# uDev_C8051.net
KiCad netlist of a schematic drawn in EAGLE
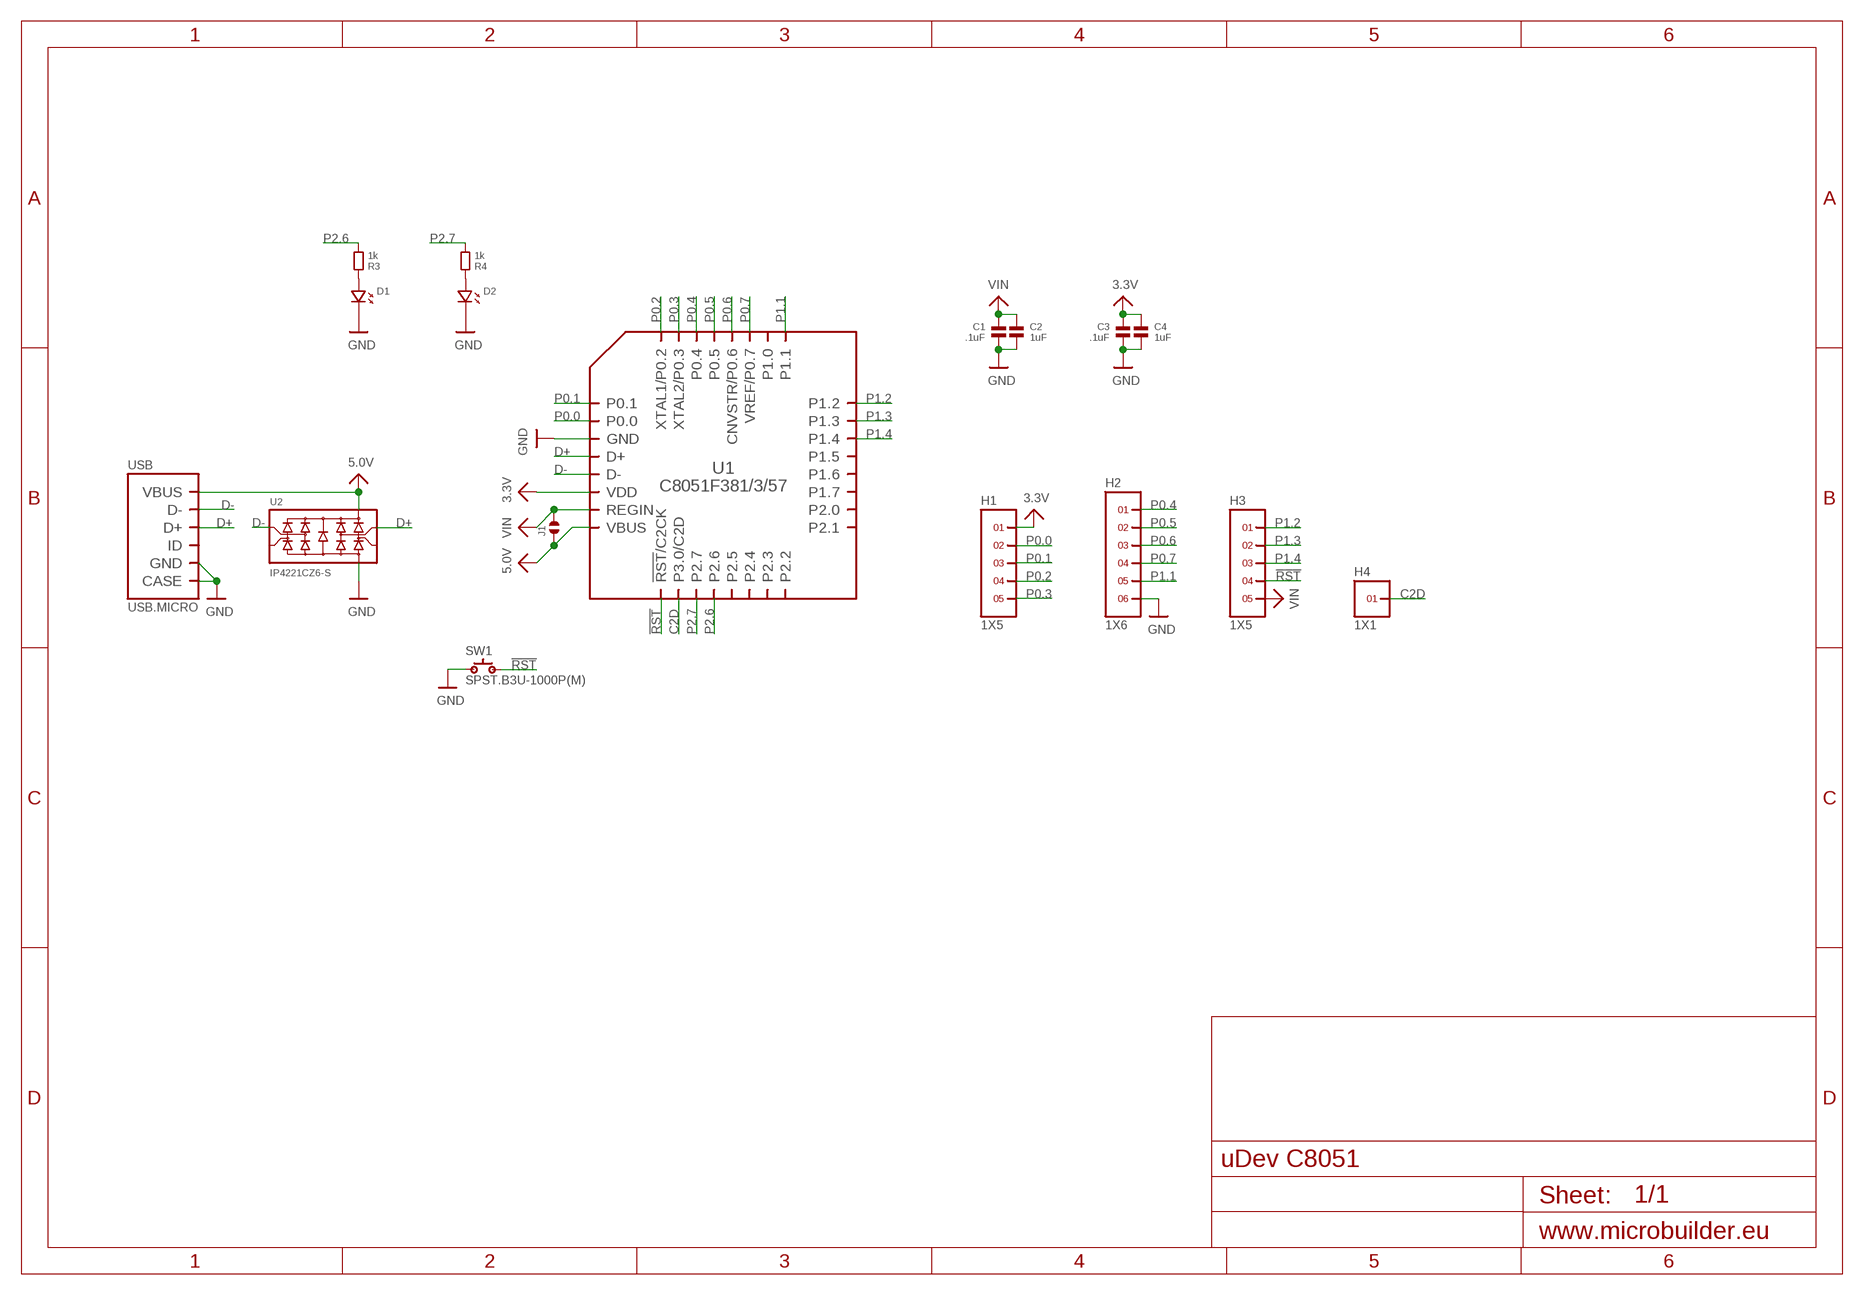
[diagram p0: schematic, sheet 1]

(export (version "E")
  (design (tool "Eeschema 10.0.6"))
  (components
    (comp (ref "C1")
      (value ".1uF")
      (footprint "eagle-import:0402")
      (libsource (lib "eagle-import") (part "CAPACITOR.0402"))
    )
    (comp (ref "C2")
      (value "1uF")
      (footprint "eagle-import:0402")
      (libsource (lib "eagle-import") (part "CAPACITOR.0402"))
    )
    (comp (ref "C3")
      (value ".1uF")
      (footprint "eagle-import:0402")
      (libsource (lib "eagle-import") (part "CAPACITOR.0402"))
    )
    (comp (ref "C4")
      (value "1uF")
      (footprint "eagle-import:0402")
      (libsource (lib "eagle-import") (part "CAPACITOR.0402"))
    )
    (comp (ref "D1")
      (value "LED.0402")
      (footprint "eagle-import:0402.LED")
      (libsource (lib "eagle-import") (part "LED.0402"))
    )
    (comp (ref "D2")
      (value "LED.0402")
      (footprint "eagle-import:0402.LED")
      (libsource (lib "eagle-import") (part "LED.0402"))
    )
    (comp (ref "H1")
      (value "1X5")
      (footprint "eagle-import:1X5")
      (libsource (lib "eagle-import") (part "1X5"))
    )
    (comp (ref "H2")
      (value "1X6")
      (footprint "eagle-import:1X6")
      (libsource (lib "eagle-import") (part "1X6"))
    )
    (comp (ref "H3")
      (value "1X5")
      (footprint "eagle-import:1X5")
      (libsource (lib "eagle-import") (part "1X5"))
    )
    (comp (ref "H4")
      (value "1X1")
      (footprint "eagle-import:1X1")
      (libsource (lib "eagle-import") (part "1X1"))
    )
    (comp (ref "J1")
      (value "SOLDERJUMPER.2.SML")
      (footprint "eagle-import:2.SML")
      (libsource (lib "eagle-import") (part "SOLDERJUMPER.2.SML"))
    )
    (comp (ref "R3")
      (value "1k")
      (footprint "eagle-import:0402")
      (libsource (lib "eagle-import") (part "RESISTOR.0402"))
    )
    (comp (ref "R4")
      (value "1k")
      (footprint "eagle-import:0402")
      (libsource (lib "eagle-import") (part "RESISTOR.0402"))
    )
    (comp (ref "SW1")
      (value "SPST.B3U-1000P(M)")
      (footprint "eagle-import:B3U-1000P(M)")
      (libsource (lib "eagle-import") (part "SPST.B3U-1000P(M)"))
    )
    (comp (ref "U1")
      (value "C8051F381/3/57")
      (footprint "eagle-import:QFN32")
      (libsource (lib "eagle-import") (part "C8051F381/3/5/7.QFN"))
    )
    (comp (ref "U2")
      (value "IP4221CZ6-S")
      (footprint "eagle-import:DFN1410-6")
      (libsource (lib "eagle-import") (part "IP4221CZ6-S"))
    )
    (comp (ref "USB")
      (value "USB.MICRO")
      (footprint "eagle-import:1554266-1")
      (libsource (lib "eagle-import") (part "USB.MICRO"))
    )
  )
  (nets
    (net (code "1") (name "/C2D") (class "Default")
      (node (ref "H4") (pin "1") (pinfunction "1_1") (pintype "bidirectional"))
      (node (ref "U1") (pin "10") (pinfunction "P3.0/C2D_10") (pintype "bidirectional"))
    )
    (net (code "2") (name "/D+") (class "Default")
      (node (ref "U1") (pin "4") (pinfunction "D+_4") (pintype "bidirectional"))
      (node (ref "U2") (pin "3") (pinfunction "3_3") (pintype "bidirectional"))
      (node (ref "USB") (pin "3") (pinfunction "D+_3") (pintype "bidirectional"))
    )
    (net (code "3") (name "/D-") (class "Default")
      (node (ref "U1") (pin "5") (pinfunction "D-_5") (pintype "bidirectional"))
      (node (ref "U2") (pin "1") (pinfunction "1_1") (pintype "bidirectional"))
      (node (ref "USB") (pin "2") (pinfunction "D-_2") (pintype "bidirectional"))
    )
    (net (code "4") (name "/P0.0") (class "Default")
      (node (ref "H1") (pin "2") (pinfunction "2_2") (pintype "bidirectional"))
      (node (ref "U1") (pin "2") (pinfunction "P0.0_2") (pintype "bidirectional"))
    )
    (net (code "5") (name "/P0.1") (class "Default")
      (node (ref "H1") (pin "3") (pinfunction "3_3") (pintype "bidirectional"))
      (node (ref "U1") (pin "1") (pinfunction "P0.1_1") (pintype "bidirectional"))
    )
    (net (code "6") (name "/P0.2") (class "Default")
      (node (ref "H1") (pin "4") (pinfunction "4_4") (pintype "bidirectional"))
      (node (ref "U1") (pin "32") (pinfunction "XTAL1/P0.2_32") (pintype "bidirectional"))
    )
    (net (code "7") (name "/P0.3") (class "Default")
      (node (ref "H1") (pin "5") (pinfunction "5_5") (pintype "bidirectional"))
      (node (ref "U1") (pin "31") (pinfunction "XTAL2/P0.3_31") (pintype "bidirectional"))
    )
    (net (code "8") (name "/P0.4") (class "Default")
      (node (ref "H2") (pin "1") (pinfunction "1_1") (pintype "bidirectional"))
      (node (ref "U1") (pin "30") (pinfunction "P0.4_30") (pintype "bidirectional"))
    )
    (net (code "9") (name "/P0.5") (class "Default")
      (node (ref "H2") (pin "2") (pinfunction "2_2") (pintype "bidirectional"))
      (node (ref "U1") (pin "29") (pinfunction "P0.5_29") (pintype "bidirectional"))
    )
    (net (code "10") (name "/P0.6") (class "Default")
      (node (ref "H2") (pin "3") (pinfunction "3_3") (pintype "bidirectional"))
      (node (ref "U1") (pin "28") (pinfunction "CNVSTR/P0.6_28") (pintype "bidirectional"))
    )
    (net (code "11") (name "/P0.7") (class "Default")
      (node (ref "H2") (pin "4") (pinfunction "4_4") (pintype "bidirectional"))
      (node (ref "U1") (pin "27") (pinfunction "VREF/P0.7_27") (pintype "bidirectional"))
    )
    (net (code "12") (name "/P1.1") (class "Default")
      (node (ref "H2") (pin "5") (pinfunction "5_5") (pintype "bidirectional"))
      (node (ref "U1") (pin "25") (pinfunction "P1.1_25") (pintype "bidirectional"))
    )
    (net (code "13") (name "/P1.2") (class "Default")
      (node (ref "H3") (pin "1") (pinfunction "1_1") (pintype "bidirectional"))
      (node (ref "U1") (pin "24") (pinfunction "P1.2_24") (pintype "bidirectional"))
    )
    (net (code "14") (name "/P1.3") (class "Default")
      (node (ref "H3") (pin "2") (pinfunction "2_2") (pintype "bidirectional"))
      (node (ref "U1") (pin "23") (pinfunction "P1.3_23") (pintype "bidirectional"))
    )
    (net (code "15") (name "/P1.4") (class "Default")
      (node (ref "H3") (pin "3") (pinfunction "3_3") (pintype "bidirectional"))
      (node (ref "U1") (pin "22") (pinfunction "P1.4_22") (pintype "bidirectional"))
    )
    (net (code "16") (name "/P2.6") (class "Default")
      (node (ref "R3") (pin "2") (pinfunction "2_2") (pintype "bidirectional"))
      (node (ref "U1") (pin "12") (pinfunction "P2.6_12") (pintype "bidirectional"))
    )
    (net (code "17") (name "/P2.7") (class "Default")
      (node (ref "R4") (pin "2") (pinfunction "2_2") (pintype "bidirectional"))
      (node (ref "U1") (pin "11") (pinfunction "P2.7_11") (pintype "bidirectional"))
    )
    (net (code "18") (name "/~{RST}") (class "Default")
      (node (ref "H3") (pin "4") (pinfunction "4_4") (pintype "bidirectional"))
      (node (ref "SW1") (pin "2") (pinfunction "2_2") (pintype "bidirectional"))
      (node (ref "U1") (pin "9") (pinfunction "~{RST}/C2CK_9") (pintype "bidirectional"))
    )
    (net (code "19") (name "3.3V") (class "Default")
      (node (ref "C3") (pin "1") (pinfunction "1_1") (pintype "bidirectional"))
      (node (ref "C4") (pin "1") (pinfunction "1_1") (pintype "bidirectional"))
      (node (ref "H1") (pin "1") (pinfunction "1_1") (pintype "bidirectional"))
      (node (ref "U1") (pin "6") (pinfunction "VDD_6") (pintype "bidirectional"))
    )
    (net (code "20") (name "5.0V") (class "Default")
      (node (ref "J1") (pin "1") (pinfunction "1_1") (pintype "bidirectional"))
      (node (ref "U1") (pin "8") (pinfunction "VBUS_8") (pintype "bidirectional"))
      (node (ref "U2") (pin "5") (pinfunction "5_5") (pintype "bidirectional"))
      (node (ref "USB") (pin "1") (pinfunction "VBUS_1") (pintype "bidirectional"))
    )
    (net (code "21") (name "GND") (class "Default")
      (node (ref "C1") (pin "2") (pinfunction "2_2") (pintype "bidirectional"))
      (node (ref "C2") (pin "2") (pinfunction "2_2") (pintype "bidirectional"))
      (node (ref "C3") (pin "2") (pinfunction "2_2") (pintype "bidirectional"))
      (node (ref "C4") (pin "2") (pinfunction "2_2") (pintype "bidirectional"))
      (node (ref "D1") (pin "P$2") (pinfunction "2_P$2") (pintype "bidirectional"))
      (node (ref "D2") (pin "P$2") (pinfunction "2_P$2") (pintype "bidirectional"))
      (node (ref "H2") (pin "6") (pinfunction "6_6") (pintype "bidirectional"))
      (node (ref "SW1") (pin "1") (pinfunction "1_1") (pintype "bidirectional"))
      (node (ref "U1") (pin "3") (pinfunction "GND_3") (pintype "bidirectional"))
      (node (ref "U1") (pin "PAD") (pinfunction "GND_PAD") (pintype "bidirectional"))
      (node (ref "U2") (pin "2") (pinfunction "2_2") (pintype "bidirectional"))
      (node (ref "USB") (pin "5") (pinfunction "GND_5") (pintype "bidirectional"))
      (node (ref "USB") (pin "PAD1@1") (pinfunction "CASE_PAD1@1") (pintype "bidirectional"))
      (node (ref "USB") (pin "PAD1@2") (pinfunction "CASE_PAD1@2") (pintype "bidirectional"))
      (node (ref "USB") (pin "PAD1@VIA1") (pinfunction "CASE_PAD1@VIA1") (pintype "bidirectional"))
      (node (ref "USB") (pin "PAD1@VIA2") (pinfunction "CASE_PAD1@VIA2") (pintype "bidirectional"))
      (node (ref "USB") (pin "PAD1@VIA3") (pinfunction "CASE_PAD1@VIA3") (pintype "bidirectional"))
      (node (ref "USB") (pin "PAD1@VIA4") (pinfunction "CASE_PAD1@VIA4") (pintype "bidirectional"))
      (node (ref "USB") (pin "PAD1@VIA5") (pinfunction "CASE_PAD1@VIA5") (pintype "bidirectional"))
      (node (ref "USB") (pin "PAD2") (pinfunction "CASE_PAD2") (pintype "bidirectional"))
      (node (ref "USB") (pin "PAD2@VIA1") (pinfunction "CASE_PAD2@VIA1") (pintype "bidirectional"))
      (node (ref "USB") (pin "PAD2@VIA2") (pinfunction "CASE_PAD2@VIA2") (pintype "bidirectional"))
      (node (ref "USB") (pin "PAD2@VIA3") (pinfunction "CASE_PAD2@VIA3") (pintype "bidirectional"))
      (node (ref "USB") (pin "PAD2@VIA4") (pinfunction "CASE_PAD2@VIA4") (pintype "bidirectional"))
      (node (ref "USB") (pin "PAD2@VIA5") (pinfunction "CASE_PAD2@VIA5") (pintype "bidirectional"))
      (node (ref "USB") (pin "PAD2@VIA6") (pinfunction "CASE_PAD2@VIA6") (pintype "bidirectional"))
      (node (ref "USB") (pin "PAD2@VIA7") (pinfunction "CASE_PAD2@VIA7") (pintype "bidirectional"))
      (node (ref "USB") (pin "PAD3") (pinfunction "CASE_PAD3") (pintype "bidirectional"))
      (node (ref "USB") (pin "PAD3@VIA1") (pinfunction "CASE_PAD3@VIA1") (pintype "bidirectional"))
      (node (ref "USB") (pin "PAD3@VIA2") (pinfunction "CASE_PAD3@VIA2") (pintype "bidirectional"))
      (node (ref "USB") (pin "PAD3@VIA3") (pinfunction "CASE_PAD3@VIA3") (pintype "bidirectional"))
      (node (ref "USB") (pin "PAD3@VIA4") (pinfunction "CASE_PAD3@VIA4") (pintype "bidirectional"))
      (node (ref "USB") (pin "PAD3@VIA5") (pinfunction "CASE_PAD3@VIA5") (pintype "bidirectional"))
      (node (ref "USB") (pin "PAD3@VIA6") (pinfunction "CASE_PAD3@VIA6") (pintype "bidirectional"))
      (node (ref "USB") (pin "PAD3@VIA7") (pinfunction "CASE_PAD3@VIA7") (pintype "bidirectional"))
      (node (ref "USB") (pin "PAD4@1") (pinfunction "CASE_PAD4@1") (pintype "bidirectional"))
      (node (ref "USB") (pin "PAD4@2") (pinfunction "CASE_PAD4@2") (pintype "bidirectional"))
      (node (ref "USB") (pin "PAD4@VIA1") (pinfunction "CASE_PAD4@VIA1") (pintype "bidirectional"))
      (node (ref "USB") (pin "PAD4@VIA2") (pinfunction "CASE_PAD4@VIA2") (pintype "bidirectional"))
      (node (ref "USB") (pin "PAD4@VIA3") (pinfunction "CASE_PAD4@VIA3") (pintype "bidirectional"))
      (node (ref "USB") (pin "PAD4@VIA4") (pinfunction "CASE_PAD4@VIA4") (pintype "bidirectional"))
      (node (ref "USB") (pin "PAD4@VIA5") (pinfunction "CASE_PAD4@VIA5") (pintype "bidirectional"))
    )
    (net (code "22") (name "Net-(D1-1)") (class "Default")
      (node (ref "D1") (pin "P$1") (pinfunction "1_P$1") (pintype "bidirectional"))
      (node (ref "R3") (pin "1") (pinfunction "1_1") (pintype "bidirectional"))
    )
    (net (code "23") (name "Net-(D2-1)") (class "Default")
      (node (ref "D2") (pin "P$1") (pinfunction "1_P$1") (pintype "bidirectional"))
      (node (ref "R4") (pin "1") (pinfunction "1_1") (pintype "bidirectional"))
    )
    (net (code "24") (name "VIN") (class "Default")
      (node (ref "C1") (pin "1") (pinfunction "1_1") (pintype "bidirectional"))
      (node (ref "C2") (pin "1") (pinfunction "1_1") (pintype "bidirectional"))
      (node (ref "H3") (pin "5") (pinfunction "5_5") (pintype "bidirectional"))
      (node (ref "J1") (pin "2") (pinfunction "2_2") (pintype "bidirectional"))
      (node (ref "U1") (pin "7") (pinfunction "REGIN_7") (pintype "bidirectional"))
    )
    (net (code "25") (name "unconnected-(U1-P1.0-Pad26)") (class "Default")
      (node (ref "U1") (pin "26") (pinfunction "P1.0_26") (pintype "bidirectional"))
    )
    (net (code "26") (name "unconnected-(U1-P1.5-Pad21)") (class "Default")
      (node (ref "U1") (pin "21") (pinfunction "P1.5_21") (pintype "bidirectional"))
    )
    (net (code "27") (name "unconnected-(U1-P1.6-Pad20)") (class "Default")
      (node (ref "U1") (pin "20") (pinfunction "P1.6_20") (pintype "bidirectional"))
    )
    (net (code "28") (name "unconnected-(U1-P1.7-Pad19)") (class "Default")
      (node (ref "U1") (pin "19") (pinfunction "P1.7_19") (pintype "bidirectional"))
    )
    (net (code "29") (name "unconnected-(U1-P2.0-Pad18)") (class "Default")
      (node (ref "U1") (pin "18") (pinfunction "P2.0_18") (pintype "bidirectional"))
    )
    (net (code "30") (name "unconnected-(U1-P2.1-Pad17)") (class "Default")
      (node (ref "U1") (pin "17") (pinfunction "P2.1_17") (pintype "bidirectional"))
    )
    (net (code "31") (name "unconnected-(U1-P2.2-Pad16)") (class "Default")
      (node (ref "U1") (pin "16") (pinfunction "P2.2_16") (pintype "bidirectional"))
    )
    (net (code "32") (name "unconnected-(U1-P2.3-Pad15)") (class "Default")
      (node (ref "U1") (pin "15") (pinfunction "P2.3_15") (pintype "bidirectional"))
    )
    (net (code "33") (name "unconnected-(U1-P2.4-Pad14)") (class "Default")
      (node (ref "U1") (pin "14") (pinfunction "P2.4_14") (pintype "bidirectional"))
    )
    (net (code "34") (name "unconnected-(U1-P2.5-Pad13)") (class "Default")
      (node (ref "U1") (pin "13") (pinfunction "P2.5_13") (pintype "bidirectional"))
    )
    (net (code "35") (name "unconnected-(U2-Pad4)") (class "Default")
      (node (ref "U2") (pin "4") (pinfunction "4_4") (pintype "bidirectional"))
    )
    (net (code "36") (name "unconnected-(U2-Pad6)") (class "Default")
      (node (ref "U2") (pin "6") (pinfunction "6_6") (pintype "bidirectional"))
    )
    (net (code "37") (name "unconnected-(USB-ID-Pad4)") (class "Default")
      (node (ref "USB") (pin "4") (pinfunction "ID_4") (pintype "bidirectional"))
    )
  )
)
